# Battery_Feed_and_Socket.net
KiCad netlist of a schematic drawn in Altium Designer
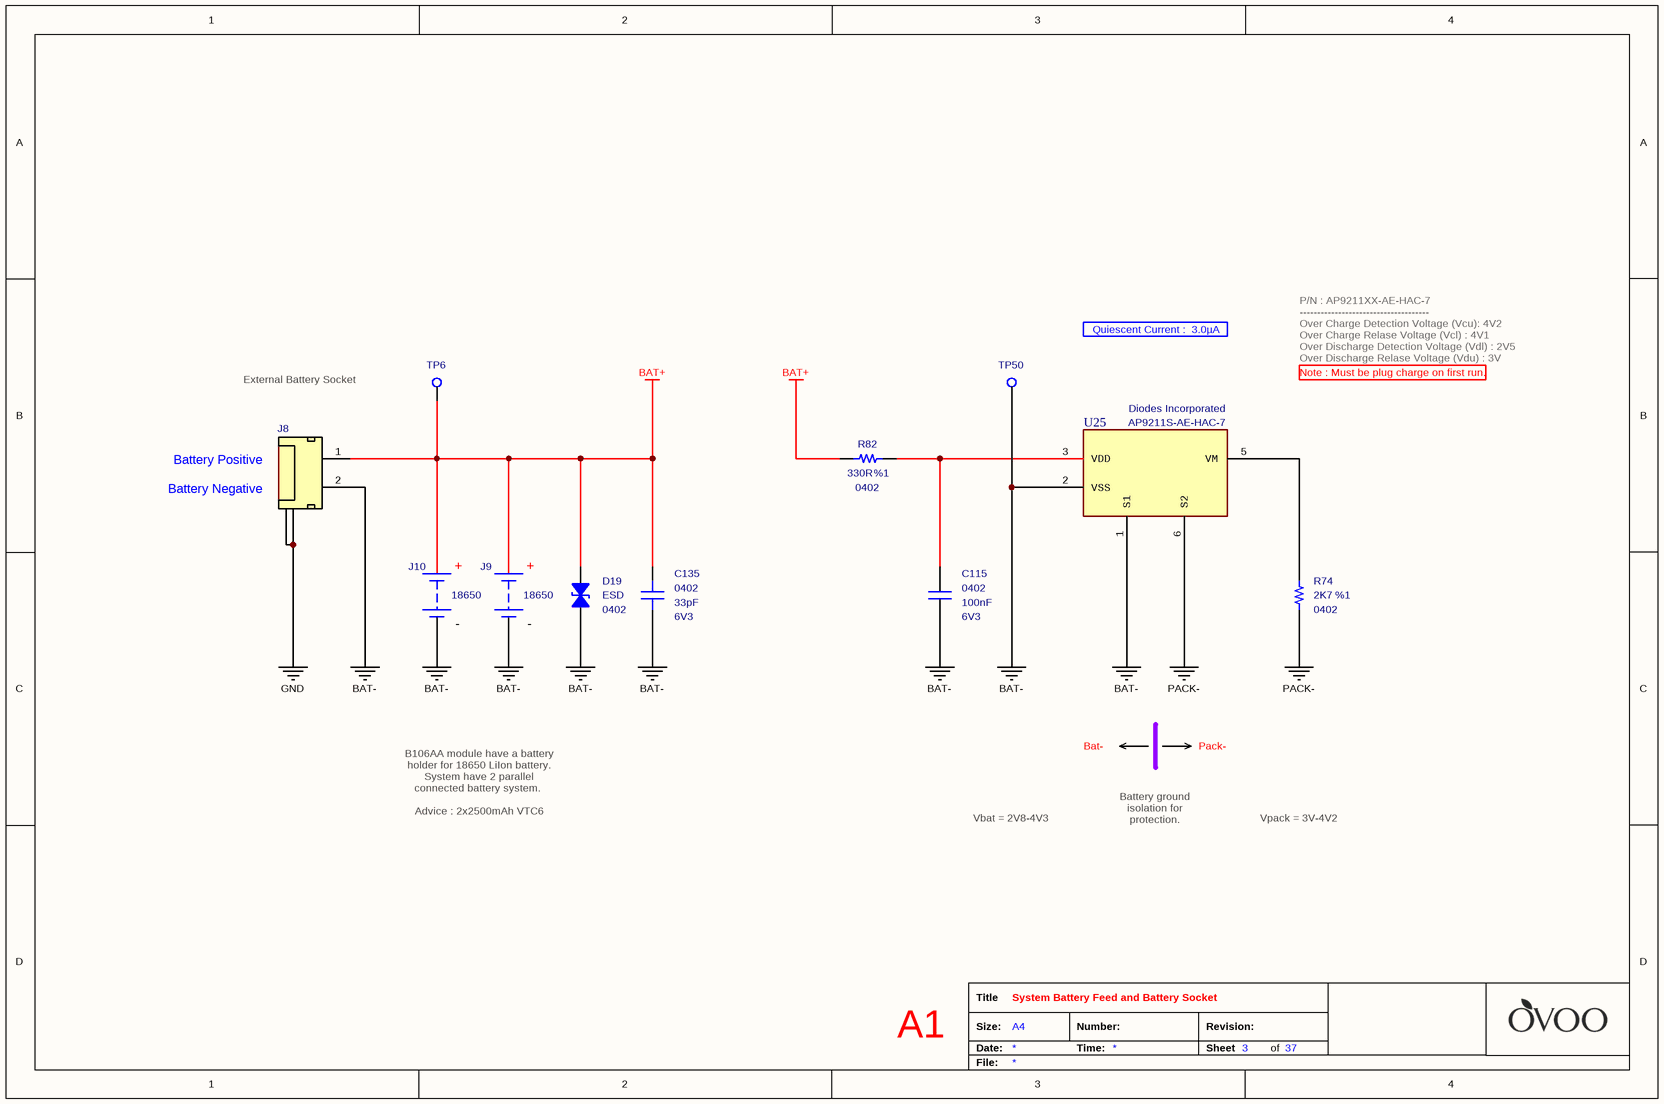
[diagram p0: Battery Feed and Socket.SchDoc]

(export (version "E")
  (design (tool "Eeschema 10.0.6"))
  (components
    (comp (ref "C115")
      (value "100nF")
      (footprint "CAPACITOR_0402")
      (description "Capacitor - 100nF [0402-6V3] (Ceramic)")
      (fields
        (field (name "MANUFACTURER_PART_NUMBER") "04026D104KAT4A")
        (field (name "MOUSER_PART_NUMBER") "581-04026D104KAT4A")
        (field (name "CASE") "0402")
        (field (name "VOLTAGE") "6V3")
      )
      (libsource (lib "Ovoo_Schematic") (part "Capacitor - 100nF [0402-6V3]"))
    )
    (comp (ref "C135")
      (value "33pF")
      (footprint "CAPACITOR_0402")
      (description "Capacitor - 33pF [0402] (Ceramic)")
      (fields
        (field (name "MANUFACTURER_PART_NUMBER") "C0402C330J9RACAUTO")
        (field (name "MOUSER_PART_NUMBER") "80-C0402C330J9RAUTO")
        (field (name "CASE") "0402")
        (field (name "VOLTAGE") "6V3")
      )
      (libsource (lib "Ovoo_Schematic") (part "Capacitor - 33pF [0402-6V3]"))
    )
    (comp (ref "D19")
      (value "ESD Suppressors")
      (footprint "ESD_0402")
      (description "TVS Diode (Bi-directional)")
      (fields
        (field (name "MANUFACTURER_PART_NUMBER") "0402ESDA-MLP1")
        (field (name "MOUSER_PART_NUMBER") "504-0402ESDA-MLP1")
        (field (name "CASE") "0402")
      )
      (libsource (lib "Ovoo_Schematic") (part "Diode - ESD Protection"))
    )
    (comp (ref "J8")
      (value "External Battery Socket")
      (footprint "Connector_Tunic 2P - H")
      (description "Mini Tunic Connector with 2P")
      (fields
        (field (name "MANUFACTURER_PART_NUMBER") "53261-0271")
        (field (name "MOUSER_PART_NUMBER") "538-53261-0271")
      )
      (libsource (lib "Ovoo_Schematic") (part "Connector - Mini Tunic 2P (1.25)"))
    )
    (comp (ref "J9")
      (value "Battery Clip Holder and Battery")
      (footprint "BATTERY_HOLDER - Bat - NoSilk")
      (description "Cylindrical Battery Contacts, Clips, Holders & Springs 16MM - 19MM SM BATTERY CLIP")
      (fields
        (field (name "MANUFACTURER_PART_NUMBER") "254")
        (field (name "MOUSER_PART_NUMBER") "534-254")
        (field (name "BATTERY SIZE") "18650")
      )
      (libsource (lib "Ovoo_Schematic") (part "Connector - Battery Clip Holder + Battery"))
    )
    (comp (ref "J10")
      (value "Battery Clip Holder and Battery")
      (footprint "BATTERY_HOLDER - Bat - NoSilk")
      (description "Cylindrical Battery Contacts, Clips, Holders & Springs 16MM - 19MM SM BATTERY CLIP")
      (fields
        (field (name "MANUFACTURER_PART_NUMBER") "254")
        (field (name "MOUSER_PART_NUMBER") "534-254")
        (field (name "BATTERY SIZE") "18650")
      )
      (libsource (lib "Ovoo_Schematic") (part "Connector - Battery Clip Holder + Battery"))
    )
    (comp (ref "R74")
      (value "2K7")
      (footprint "RESISTOR_0402")
      (description "Thick Film Resistors - SMD 1/16 W 2.7 Kohms 1%")
      (fields
        (field (name "MANUFACTURER_PART_NUMBER") "CRCW04022K70FKED")
        (field (name "MOUSER_PART_NUMBER") "71-CRCW0402-2.7K-E3")
        (field (name "CASE") "0402")
        (field (name "TOLERANCE") "%1")
      )
      (libsource (lib "Ovoo_Schematic") (part "Resistor - 2K7"))
    )
    (comp (ref "R82")
      (value "330R")
      (footprint "RESISTOR_0402")
      (description "Thick Film Resistors - SMD 1/16 W 330 Ohm 1%")
      (fields
        (field (name "MANUFACTURER_PART_NUMBER") "CRCW0402330RFKED")
        (field (name "MOUSER_PART_NUMBER") "71-CRCW0402-330-E3")
        (field (name "TOLERANCE") "%1")
        (field (name "CASE") "0402")
      )
      (libsource (lib "Ovoo_Schematic") (part "Resistor - 330R"))
    )
    (comp (ref "TP6")
      (value "PCB - Test Point")
      (footprint "Test_Pad - Hole")
      (description "Test Point")
      (libsource (lib "Ovoo_Schematic") (part "PCB - Test Point"))
    )
    (comp (ref "TP50")
      (value "PCB - Test Point")
      (footprint "Test_Pad - Hole")
      (description "Test Point")
      (libsource (lib "Ovoo_Schematic") (part "PCB - Test Point"))
    )
    (comp (ref "U25")
      (value "Battery Management IC")
      (footprint "AP9211")
      (description "Battery Management SGL Chip Protection 12Vdss 12Vgss 1000mW")
      (fields
        (field (name "MOUSER_PART_NUMBER") "621-AP9211S-AE-HAC-7")
        (field (name "MANUFACTURER_PART_NUMBER") "AP9211S-AE-HAC-7")
        (field (name "MANUFACTURER_NAME") "Diodes Incorporated")
      )
      (libsource (lib "Ovoo_Schematic") (part "IC - AP9211"))
    )
  )
  (nets
    (net (code "1") (name "BAT+") (class "Default")
      (node (ref "C135") (pin "2") (pinfunction "2_2") (pintype "passive"))
      (node (ref "D19") (pin "2") (pinfunction "2_2") (pintype "passive"))
      (node (ref "J10") (pin "1") (pinfunction "BAT+_1") (pintype "power_in"))
      (node (ref "J8") (pin "1") (pinfunction "BAT+_1") (pintype "power_in"))
      (node (ref "J9") (pin "1") (pinfunction "BAT+_1") (pintype "power_in"))
      (node (ref "R82") (pin "2") (pinfunction "2_2") (pintype "passive"))
      (node (ref "TP6") (pin "1") (pinfunction "1_1") (pintype "passive"))
    )
    (net (code "2") (name "BAT-") (class "Default")
      (node (ref "C115") (pin "2") (pinfunction "2_2") (pintype "passive"))
      (node (ref "C135") (pin "1") (pinfunction "1_1") (pintype "passive"))
      (node (ref "D19") (pin "1") (pinfunction "1_1") (pintype "passive"))
      (node (ref "J10") (pin "2") (pinfunction "BAT-_2") (pintype "power_in"))
      (node (ref "J8") (pin "2") (pinfunction "BAT-_2") (pintype "power_in"))
      (node (ref "J9") (pin "2") (pinfunction "BAT-_2") (pintype "power_in"))
      (node (ref "TP50") (pin "1") (pinfunction "1_1") (pintype "passive"))
      (node (ref "U25") (pin "1") (pinfunction "S1_1") (pintype "power_in"))
      (node (ref "U25") (pin "2") (pinfunction "VSS_2") (pintype "power_in"))
    )
    (net (code "3") (name "GND") (class "Default")
      (node (ref "J8") (pin "3") (pinfunction "Termination_3") (pintype "passive"))
      (node (ref "J8") (pin "4") (pinfunction "Termination_4") (pintype "passive"))
    )
    (net (code "4") (name "Net-(U25-VDD)") (class "Default")
      (node (ref "C115") (pin "1") (pinfunction "1_1") (pintype "passive"))
      (node (ref "R82") (pin "1") (pinfunction "1_1") (pintype "passive"))
      (node (ref "U25") (pin "3") (pinfunction "VDD_3") (pintype "power_in"))
    )
    (net (code "5") (name "Net-(U25-VM)") (class "Default")
      (node (ref "R74") (pin "2") (pinfunction "2_2") (pintype "passive"))
      (node (ref "U25") (pin "5") (pinfunction "VM_5") (pintype "power_in"))
    )
    (net (code "6") (name "PACK-") (class "Default")
      (node (ref "R74") (pin "1") (pinfunction "1_1") (pintype "passive"))
      (node (ref "U25") (pin "6") (pinfunction "S2_6") (pintype "power_in"))
    )
  )
)
